# Connectors.net
KiCad netlist of a schematic drawn in Altium Designer
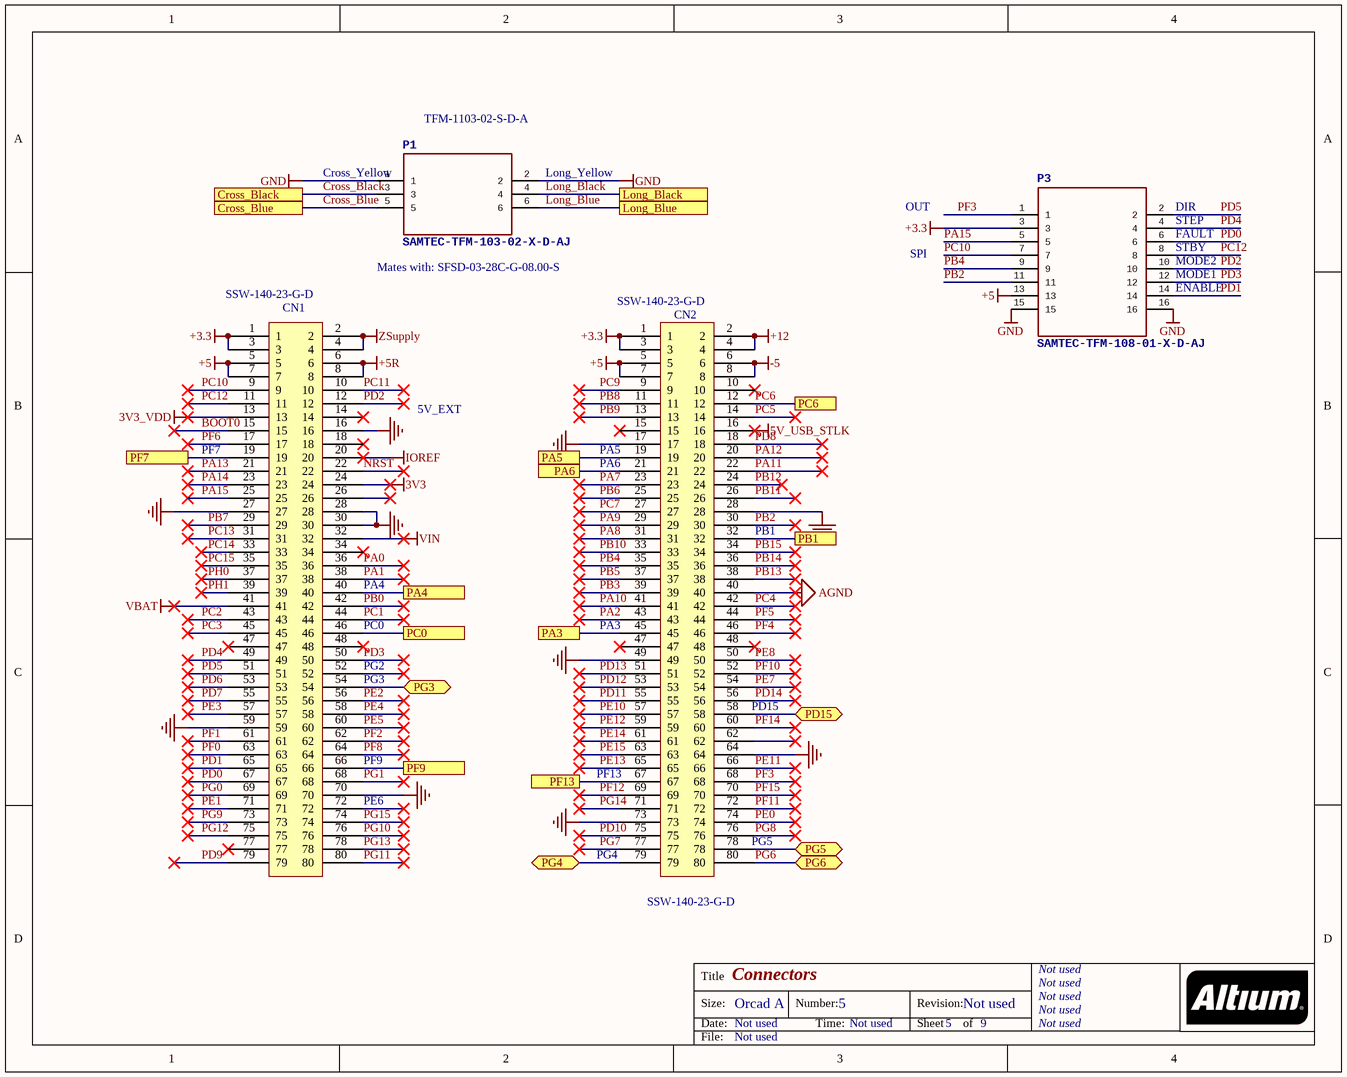
[diagram p0: Connectors.SchDoc]

(export (version "E")
  (design (tool "Eeschema 10.0.6"))
  (components
    (comp (ref "CN1")
      (value "SSW-140-23-G-D")
      (footprint "SSW-140-23-G-D")
      (description "80 Position Receptacle Connector Through Hole")
      (fields (field (name "SUPPLIER PART NUMBER 1") "SSW-140-23-G-D") (field (name "MANUFACTURER") "Samtec"))
      (libsource (lib "ZLS_Schematic_lib") (part "SSW-140-23-G-D"))
    )
    (comp (ref "CN2")
      (value "SSW-140-23-G-D")
      (footprint "SSW-140-23-G-D")
      (description "80 Position Receptacle Connector Through Hole")
      (fields (field (name "SUPPLIER PART NUMBER 1") "SSW-140-23-G-D") (field (name "MANUFACTURER") "Samtec"))
      (libsource (lib "ZLS_Schematic_lib") (part "SSW-140-23-G-D"))
    )
    (comp (ref "P1")
      (value "SAMTEC-TFM-103-02-X-D-AJ")
      (footprint "SAMTEC-TFM-103-02-X-D-A")
      (libsource (lib "SAMTEC-TFM-103-02-X-D-A") (part "SAMTEC-TFM-103-02-X-D-AJ"))
    )
    (comp (ref "P3")
      (value "SAMTEC-TFM-108-01-X-D-AJ")
      (footprint "SAMTEC-TFM-108-01-X-D-A")
      (libsource (lib "SAMTEC-TFM-108-01-X-D-A") (part "SAMTEC-TFM-108-01-X-D-AJ"))
    )
  )
  (nets
    (net (code "1") (name "+3.3") (class "Default")
      (node (ref "CN1") (pin "1") (pinfunction "1_1") (pintype "passive"))
      (node (ref "CN1") (pin "3") (pinfunction "3_3") (pintype "passive"))
      (node (ref "CN2") (pin "1") (pinfunction "1_1") (pintype "passive"))
      (node (ref "CN2") (pin "3") (pinfunction "3_3") (pintype "passive"))
      (node (ref "P3") (pin "3") (pinfunction "3_3") (pintype "passive"))
    )
    (net (code "2") (name "+5") (class "Default")
      (node (ref "CN1") (pin "5") (pinfunction "5_5") (pintype "passive"))
      (node (ref "CN1") (pin "7") (pinfunction "7_7") (pintype "passive"))
      (node (ref "CN2") (pin "5") (pinfunction "5_5") (pintype "passive"))
      (node (ref "CN2") (pin "7") (pinfunction "7_7") (pintype "passive"))
      (node (ref "P3") (pin "13") (pinfunction "13_13") (pintype "passive"))
    )
    (net (code "3") (name "+5R") (class "Default")
      (node (ref "CN1") (pin "6") (pinfunction "6_6") (pintype "passive"))
      (node (ref "CN1") (pin "8") (pinfunction "8_8") (pintype "passive"))
    )
    (net (code "4") (name "+12") (class "Default")
      (node (ref "CN2") (pin "2") (pinfunction "2_2") (pintype "passive"))
      (node (ref "CN2") (pin "4") (pinfunction "4_4") (pintype "passive"))
    )
    (net (code "5") (name "-5") (class "Default")
      (node (ref "CN2") (pin "6") (pinfunction "6_6") (pintype "passive"))
      (node (ref "CN2") (pin "8") (pinfunction "8_8") (pintype "passive"))
    )
    (net (code "6") (name "/BOOT0") (class "Default")
      (node (ref "CN1") (pin "15") (pinfunction "15_15") (pintype "passive+no_connect"))
    )
    (net (code "7") (name "/Cross_Black") (class "Default")
      (node (ref "P1") (pin "3") (pinfunction "3_3") (pintype "passive"))
    )
    (net (code "8") (name "/Cross_Blue") (class "Default")
      (node (ref "P1") (pin "5") (pinfunction "5_5") (pintype "passive"))
    )
    (net (code "9") (name "/Long_Black") (class "Default")
      (node (ref "P1") (pin "4") (pinfunction "4_4") (pintype "passive"))
    )
    (net (code "10") (name "/Long_Blue") (class "Default")
      (node (ref "P1") (pin "6") (pinfunction "6_6") (pintype "passive"))
    )
    (net (code "11") (name "/NRST") (class "Default")
      (node (ref "CN1") (pin "22") (pinfunction "22_22") (pintype "passive+no_connect"))
    )
    (net (code "12") (name "/PA0") (class "Default")
      (node (ref "CN1") (pin "36") (pinfunction "36_36") (pintype "passive+no_connect"))
    )
    (net (code "13") (name "/PA1") (class "Default")
      (node (ref "CN1") (pin "38") (pinfunction "38_38") (pintype "passive+no_connect"))
    )
    (net (code "14") (name "/PA2") (class "Default")
      (node (ref "CN2") (pin "43") (pinfunction "43_43") (pintype "passive+no_connect"))
    )
    (net (code "15") (name "/PA3") (class "Default")
      (node (ref "CN2") (pin "45") (pinfunction "45_45") (pintype "passive"))
    )
    (net (code "16") (name "/PA4") (class "Default")
      (node (ref "CN1") (pin "40") (pinfunction "40_40") (pintype "passive"))
    )
    (net (code "17") (name "/PA5") (class "Default")
      (node (ref "CN2") (pin "19") (pinfunction "19_19") (pintype "passive"))
    )
    (net (code "18") (name "/PA6") (class "Default")
      (node (ref "CN2") (pin "21") (pinfunction "21_21") (pintype "passive"))
    )
    (net (code "19") (name "/PA7") (class "Default")
      (node (ref "CN2") (pin "23") (pinfunction "23_23") (pintype "passive+no_connect"))
    )
    (net (code "20") (name "/PA8") (class "Default")
      (node (ref "CN2") (pin "31") (pinfunction "31_31") (pintype "passive+no_connect"))
    )
    (net (code "21") (name "/PA9") (class "Default")
      (node (ref "CN2") (pin "29") (pinfunction "29_29") (pintype "passive+no_connect"))
    )
    (net (code "22") (name "/PA10") (class "Default")
      (node (ref "CN2") (pin "41") (pinfunction "41_41") (pintype "passive+no_connect"))
    )
    (net (code "23") (name "/PA11") (class "Default")
      (node (ref "CN2") (pin "22") (pinfunction "22_22") (pintype "passive+no_connect"))
    )
    (net (code "24") (name "/PA12") (class "Default")
      (node (ref "CN2") (pin "20") (pinfunction "20_20") (pintype "passive+no_connect"))
    )
    (net (code "25") (name "/PA13") (class "Default")
      (node (ref "CN1") (pin "21") (pinfunction "21_21") (pintype "passive+no_connect"))
    )
    (net (code "26") (name "/PA14") (class "Default")
      (node (ref "CN1") (pin "23") (pinfunction "23_23") (pintype "passive+no_connect"))
    )
    (net (code "27") (name "/PA15") (class "Default")
      (node (ref "CN1") (pin "25") (pinfunction "25_25") (pintype "passive"))
      (node (ref "P3") (pin "5") (pinfunction "5_5") (pintype "passive"))
    )
    (net (code "28") (name "/PB0") (class "Default")
      (node (ref "CN1") (pin "42") (pinfunction "42_42") (pintype "passive+no_connect"))
    )
    (net (code "29") (name "/PB1") (class "Default")
      (node (ref "CN2") (pin "32") (pinfunction "32_32") (pintype "passive"))
    )
    (net (code "30") (name "/PB2") (class "Default")
      (node (ref "CN2") (pin "30") (pinfunction "30_30") (pintype "passive"))
      (node (ref "P3") (pin "11") (pinfunction "11_11") (pintype "passive"))
    )
    (net (code "31") (name "/PB3") (class "Default")
      (node (ref "CN2") (pin "39") (pinfunction "39_39") (pintype "passive+no_connect"))
    )
    (net (code "32") (name "/PB4") (class "Default")
      (node (ref "CN2") (pin "35") (pinfunction "35_35") (pintype "passive"))
      (node (ref "P3") (pin "9") (pinfunction "9_9") (pintype "passive"))
    )
    (net (code "33") (name "/PB5") (class "Default")
      (node (ref "CN2") (pin "37") (pinfunction "37_37") (pintype "passive+no_connect"))
    )
    (net (code "34") (name "/PB6") (class "Default")
      (node (ref "CN2") (pin "25") (pinfunction "25_25") (pintype "passive+no_connect"))
    )
    (net (code "35") (name "/PB7") (class "Default")
      (node (ref "CN1") (pin "29") (pinfunction "29_29") (pintype "passive+no_connect"))
    )
    (net (code "36") (name "/PB8") (class "Default")
      (node (ref "CN2") (pin "11") (pinfunction "11_11") (pintype "passive+no_connect"))
    )
    (net (code "37") (name "/PB9") (class "Default")
      (node (ref "CN2") (pin "13") (pinfunction "13_13") (pintype "passive+no_connect"))
    )
    (net (code "38") (name "/PB10") (class "Default")
      (node (ref "CN2") (pin "33") (pinfunction "33_33") (pintype "passive+no_connect"))
    )
    (net (code "39") (name "/PB11") (class "Default")
      (node (ref "CN2") (pin "26") (pinfunction "26_26") (pintype "passive+no_connect"))
    )
    (net (code "40") (name "/PB12") (class "Default")
      (node (ref "CN2") (pin "24") (pinfunction "24_24") (pintype "passive+no_connect"))
    )
    (net (code "41") (name "/PB13") (class "Default")
      (node (ref "CN2") (pin "38") (pinfunction "38_38") (pintype "passive+no_connect"))
    )
    (net (code "42") (name "/PB14") (class "Default")
      (node (ref "CN2") (pin "36") (pinfunction "36_36") (pintype "passive+no_connect"))
    )
    (net (code "43") (name "/PB15") (class "Default")
      (node (ref "CN2") (pin "34") (pinfunction "34_34") (pintype "passive+no_connect"))
    )
    (net (code "44") (name "/PC0") (class "Default")
      (node (ref "CN1") (pin "46") (pinfunction "46_46") (pintype "passive"))
    )
    (net (code "45") (name "/PC1") (class "Default")
      (node (ref "CN1") (pin "44") (pinfunction "44_44") (pintype "passive+no_connect"))
    )
    (net (code "46") (name "/PC2") (class "Default")
      (node (ref "CN1") (pin "43") (pinfunction "43_43") (pintype "passive+no_connect"))
    )
    (net (code "47") (name "/PC3") (class "Default")
      (node (ref "CN1") (pin "45") (pinfunction "45_45") (pintype "passive+no_connect"))
    )
    (net (code "48") (name "/PC4") (class "Default")
      (node (ref "CN2") (pin "42") (pinfunction "42_42") (pintype "passive+no_connect"))
    )
    (net (code "49") (name "/PC5") (class "Default")
      (node (ref "CN2") (pin "14") (pinfunction "14_14") (pintype "passive+no_connect"))
    )
    (net (code "50") (name "/PC6") (class "Default")
      (node (ref "CN2") (pin "12") (pinfunction "12_12") (pintype "passive"))
    )
    (net (code "51") (name "/PC7") (class "Default")
      (node (ref "CN2") (pin "27") (pinfunction "27_27") (pintype "passive+no_connect"))
    )
    (net (code "52") (name "/PC9") (class "Default")
      (node (ref "CN2") (pin "9") (pinfunction "9_9") (pintype "passive+no_connect"))
    )
    (net (code "53") (name "/PC10") (class "Default")
      (node (ref "CN1") (pin "9") (pinfunction "9_9") (pintype "passive"))
      (node (ref "P3") (pin "7") (pinfunction "7_7") (pintype "passive"))
    )
    (net (code "54") (name "/PC11") (class "Default")
      (node (ref "CN1") (pin "10") (pinfunction "10_10") (pintype "passive+no_connect"))
    )
    (net (code "55") (name "/PC12") (class "Default")
      (node (ref "CN1") (pin "11") (pinfunction "11_11") (pintype "passive"))
      (node (ref "P3") (pin "8") (pinfunction "8_8") (pintype "passive"))
    )
    (net (code "56") (name "/PC13") (class "Default")
      (node (ref "CN1") (pin "31") (pinfunction "31_31") (pintype "passive+no_connect"))
    )
    (net (code "57") (name "/PC14") (class "Default")
      (node (ref "CN1") (pin "33") (pinfunction "33_33") (pintype "passive+no_connect"))
    )
    (net (code "58") (name "/PC15") (class "Default")
      (node (ref "CN1") (pin "35") (pinfunction "35_35") (pintype "passive+no_connect"))
    )
    (net (code "59") (name "/PD0") (class "Default")
      (node (ref "CN1") (pin "67") (pinfunction "67_67") (pintype "passive"))
      (node (ref "P3") (pin "6") (pinfunction "6_6") (pintype "passive"))
    )
    (net (code "60") (name "/PD1") (class "Default")
      (node (ref "CN1") (pin "65") (pinfunction "65_65") (pintype "passive"))
      (node (ref "P3") (pin "14") (pinfunction "14_14") (pintype "passive"))
    )
    (net (code "61") (name "/PD2") (class "Default")
      (node (ref "CN1") (pin "12") (pinfunction "12_12") (pintype "passive"))
      (node (ref "P3") (pin "10") (pinfunction "10_10") (pintype "passive"))
    )
    (net (code "62") (name "/PD3") (class "Default")
      (node (ref "CN1") (pin "50") (pinfunction "50_50") (pintype "passive"))
      (node (ref "P3") (pin "12") (pinfunction "12_12") (pintype "passive"))
    )
    (net (code "63") (name "/PD4") (class "Default")
      (node (ref "CN1") (pin "49") (pinfunction "49_49") (pintype "passive"))
      (node (ref "P3") (pin "4") (pinfunction "4_4") (pintype "passive"))
    )
    (net (code "64") (name "/PD5") (class "Default")
      (node (ref "CN1") (pin "51") (pinfunction "51_51") (pintype "passive"))
      (node (ref "P3") (pin "2") (pinfunction "2_2") (pintype "passive"))
    )
    (net (code "65") (name "/PD6") (class "Default")
      (node (ref "CN1") (pin "53") (pinfunction "53_53") (pintype "passive+no_connect"))
    )
    (net (code "66") (name "/PD7") (class "Default")
      (node (ref "CN1") (pin "55") (pinfunction "55_55") (pintype "passive+no_connect"))
    )
    (net (code "67") (name "/PD8") (class "Default")
      (node (ref "CN2") (pin "18") (pinfunction "18_18") (pintype "passive+no_connect"))
    )
    (net (code "68") (name "/PD9") (class "Default")
      (node (ref "CN1") (pin "79") (pinfunction "79_79") (pintype "passive+no_connect"))
    )
    (net (code "69") (name "/PD10") (class "Default")
      (node (ref "CN2") (pin "75") (pinfunction "75_75") (pintype "passive+no_connect"))
    )
    (net (code "70") (name "/PD11") (class "Default")
      (node (ref "CN2") (pin "55") (pinfunction "55_55") (pintype "passive+no_connect"))
    )
    (net (code "71") (name "/PD12") (class "Default")
      (node (ref "CN2") (pin "53") (pinfunction "53_53") (pintype "passive+no_connect"))
    )
    (net (code "72") (name "/PD13") (class "Default")
      (node (ref "CN2") (pin "51") (pinfunction "51_51") (pintype "passive+no_connect"))
    )
    (net (code "73") (name "/PD14") (class "Default")
      (node (ref "CN2") (pin "56") (pinfunction "56_56") (pintype "passive+no_connect"))
    )
    (net (code "74") (name "/PD15") (class "Default")
      (node (ref "CN2") (pin "58") (pinfunction "58_58") (pintype "passive"))
    )
    (net (code "75") (name "/PE0") (class "Default")
      (node (ref "CN2") (pin "74") (pinfunction "74_74") (pintype "passive+no_connect"))
    )
    (net (code "76") (name "/PE1") (class "Default")
      (node (ref "CN1") (pin "71") (pinfunction "71_71") (pintype "passive+no_connect"))
    )
    (net (code "77") (name "/PE2") (class "Default")
      (node (ref "CN1") (pin "56") (pinfunction "56_56") (pintype "passive+no_connect"))
    )
    (net (code "78") (name "/PE3") (class "Default")
      (node (ref "CN1") (pin "57") (pinfunction "57_57") (pintype "passive+no_connect"))
    )
    (net (code "79") (name "/PE4") (class "Default")
      (node (ref "CN1") (pin "58") (pinfunction "58_58") (pintype "passive+no_connect"))
    )
    (net (code "80") (name "/PE5") (class "Default")
      (node (ref "CN1") (pin "60") (pinfunction "60_60") (pintype "passive+no_connect"))
    )
    (net (code "81") (name "/PE7") (class "Default")
      (node (ref "CN2") (pin "54") (pinfunction "54_54") (pintype "passive+no_connect"))
    )
    (net (code "82") (name "/PE8") (class "Default")
      (node (ref "CN2") (pin "50") (pinfunction "50_50") (pintype "passive+no_connect"))
    )
    (net (code "83") (name "/PE10") (class "Default")
      (node (ref "CN2") (pin "57") (pinfunction "57_57") (pintype "passive+no_connect"))
    )
    (net (code "84") (name "/PE11") (class "Default")
      (node (ref "CN2") (pin "66") (pinfunction "66_66") (pintype "passive+no_connect"))
    )
    (net (code "85") (name "/PE12") (class "Default")
      (node (ref "CN2") (pin "59") (pinfunction "59_59") (pintype "passive+no_connect"))
    )
    (net (code "86") (name "/PE13") (class "Default")
      (node (ref "CN2") (pin "65") (pinfunction "65_65") (pintype "passive+no_connect"))
    )
    (net (code "87") (name "/PE14") (class "Default")
      (node (ref "CN2") (pin "61") (pinfunction "61_61") (pintype "passive+no_connect"))
    )
    (net (code "88") (name "/PE15") (class "Default")
      (node (ref "CN2") (pin "63") (pinfunction "63_63") (pintype "passive+no_connect"))
    )
    (net (code "89") (name "/PF0") (class "Default")
      (node (ref "CN1") (pin "63") (pinfunction "63_63") (pintype "passive+no_connect"))
    )
    (net (code "90") (name "/PF1") (class "Default")
      (node (ref "CN1") (pin "61") (pinfunction "61_61") (pintype "passive+no_connect"))
    )
    (net (code "91") (name "/PF2") (class "Default")
      (node (ref "CN1") (pin "62") (pinfunction "62_62") (pintype "passive+no_connect"))
    )
    (net (code "92") (name "/PF3") (class "Default")
      (node (ref "CN2") (pin "68") (pinfunction "68_68") (pintype "passive"))
      (node (ref "P3") (pin "1") (pinfunction "1_1") (pintype "passive"))
    )
    (net (code "93") (name "/PF4") (class "Default")
      (node (ref "CN2") (pin "46") (pinfunction "46_46") (pintype "passive+no_connect"))
    )
    (net (code "94") (name "/PF5") (class "Default")
      (node (ref "CN2") (pin "44") (pinfunction "44_44") (pintype "passive+no_connect"))
    )
    (net (code "95") (name "/PF6") (class "Default")
      (node (ref "CN1") (pin "17") (pinfunction "17_17") (pintype "passive+no_connect"))
    )
    (net (code "96") (name "/PF7") (class "Default")
      (node (ref "CN1") (pin "19") (pinfunction "19_19") (pintype "passive"))
    )
    (net (code "97") (name "/PF8") (class "Default")
      (node (ref "CN1") (pin "64") (pinfunction "64_64") (pintype "passive+no_connect"))
    )
    (net (code "98") (name "/PF9") (class "Default")
      (node (ref "CN1") (pin "66") (pinfunction "66_66") (pintype "passive"))
    )
    (net (code "99") (name "/PF10") (class "Default")
      (node (ref "CN2") (pin "52") (pinfunction "52_52") (pintype "passive+no_connect"))
    )
    (net (code "100") (name "/PF11") (class "Default")
      (node (ref "CN2") (pin "72") (pinfunction "72_72") (pintype "passive+no_connect"))
    )
    (net (code "101") (name "/PF12") (class "Default")
      (node (ref "CN2") (pin "69") (pinfunction "69_69") (pintype "passive+no_connect"))
    )
    (net (code "102") (name "/PF13") (class "Default")
      (node (ref "CN2") (pin "67") (pinfunction "67_67") (pintype "passive"))
    )
    (net (code "103") (name "/PF14") (class "Default")
      (node (ref "CN2") (pin "60") (pinfunction "60_60") (pintype "passive+no_connect"))
    )
    (net (code "104") (name "/PF15") (class "Default")
      (node (ref "CN2") (pin "70") (pinfunction "70_70") (pintype "passive+no_connect"))
    )
    (net (code "105") (name "/PG0") (class "Default")
      (node (ref "CN1") (pin "69") (pinfunction "69_69") (pintype "passive+no_connect"))
    )
    (net (code "106") (name "/PG1") (class "Default")
      (node (ref "CN1") (pin "68") (pinfunction "68_68") (pintype "passive+no_connect"))
    )
    (net (code "107") (name "/PG3") (class "Default")
      (node (ref "CN1") (pin "54") (pinfunction "54_54") (pintype "passive"))
    )
    (net (code "108") (name "/PG4") (class "Default")
      (node (ref "CN2") (pin "79") (pinfunction "79_79") (pintype "passive"))
    )
    (net (code "109") (name "/PG5") (class "Default")
      (node (ref "CN2") (pin "78") (pinfunction "78_78") (pintype "passive"))
    )
    (net (code "110") (name "/PG6") (class "Default")
      (node (ref "CN2") (pin "80") (pinfunction "80_80") (pintype "passive"))
    )
    (net (code "111") (name "/PG7") (class "Default")
      (node (ref "CN2") (pin "77") (pinfunction "77_77") (pintype "passive+no_connect"))
    )
    (net (code "112") (name "/PG8") (class "Default")
      (node (ref "CN2") (pin "76") (pinfunction "76_76") (pintype "passive+no_connect"))
    )
    (net (code "113") (name "/PG9") (class "Default")
      (node (ref "CN1") (pin "73") (pinfunction "73_73") (pintype "passive+no_connect"))
    )
    (net (code "114") (name "/PG10") (class "Default")
      (node (ref "CN1") (pin "76") (pinfunction "76_76") (pintype "passive+no_connect"))
    )
    (net (code "115") (name "/PG11") (class "Default")
      (node (ref "CN1") (pin "80") (pinfunction "80_80") (pintype "passive+no_connect"))
    )
    (net (code "116") (name "/PG12") (class "Default")
      (node (ref "CN1") (pin "75") (pinfunction "75_75") (pintype "passive+no_connect"))
    )
    (net (code "117") (name "/PG13") (class "Default")
      (node (ref "CN1") (pin "78") (pinfunction "78_78") (pintype "passive+no_connect"))
    )
    (net (code "118") (name "/PG14") (class "Default")
      (node (ref "CN2") (pin "71") (pinfunction "71_71") (pintype "passive+no_connect"))
    )
    (net (code "119") (name "/PG15") (class "Default")
      (node (ref "CN1") (pin "74") (pinfunction "74_74") (pintype "passive+no_connect"))
    )
    (net (code "120") (name "/PH0") (class "Default")
      (node (ref "CN1") (pin "37") (pinfunction "37_37") (pintype "passive+no_connect"))
    )
    (net (code "121") (name "/PH1") (class "Default")
      (node (ref "CN1") (pin "39") (pinfunction "39_39") (pintype "passive+no_connect"))
    )
    (net (code "122") (name "3V3") (class "Default")
      (node (ref "CN1") (pin "24") (pinfunction "24_24") (pintype "passive"))
    )
    (net (code "123") (name "3V3_VDD") (class "Default")
      (node (ref "CN1") (pin "13") (pinfunction "13_13") (pintype "passive"))
    )
    (net (code "124") (name "5V_USB_STLK") (class "Default")
      (node (ref "CN2") (pin "16") (pinfunction "16_16") (pintype "passive"))
    )
    (net (code "125") (name "AGND") (class "Default")
      (node (ref "CN2") (pin "40") (pinfunction "40_40") (pintype "passive"))
    )
    (net (code "126") (name "GND") (class "Default")
      (node (ref "CN1") (pin "16") (pinfunction "16_16") (pintype "passive"))
      (node (ref "CN1") (pin "27") (pinfunction "27_27") (pintype "passive"))
      (node (ref "CN1") (pin "28") (pinfunction "28_28") (pintype "passive"))
      (node (ref "CN1") (pin "30") (pinfunction "30_30") (pintype "passive"))
      (node (ref "CN1") (pin "59") (pinfunction "59_59") (pintype "passive"))
      (node (ref "CN1") (pin "70") (pinfunction "70_70") (pintype "passive"))
      (node (ref "CN2") (pin "17") (pinfunction "17_17") (pintype "passive"))
      (node (ref "CN2") (pin "28") (pinfunction "28_28") (pintype "passive"))
      (node (ref "CN2") (pin "49") (pinfunction "49_49") (pintype "passive"))
      (node (ref "CN2") (pin "64") (pinfunction "64_64") (pintype "passive"))
      (node (ref "CN2") (pin "73") (pinfunction "73_73") (pintype "passive"))
      (node (ref "P1") (pin "1") (pinfunction "1_1") (pintype "passive"))
      (node (ref "P1") (pin "2") (pinfunction "2_2") (pintype "passive"))
      (node (ref "P3") (pin "15") (pinfunction "15_15") (pintype "passive"))
      (node (ref "P3") (pin "16") (pinfunction "16_16") (pintype "passive"))
    )
    (net (code "127") (name "IOREF") (class "Default")
      (node (ref "CN1") (pin "20") (pinfunction "20_20") (pintype "passive"))
    )
    (net (code "128") (name "VBAT") (class "Default")
      (node (ref "CN1") (pin "41") (pinfunction "41_41") (pintype "passive"))
    )
    (net (code "129") (name "VIN") (class "Default")
      (node (ref "CN1") (pin "32") (pinfunction "32_32") (pintype "passive"))
    )
    (net (code "130") (name "ZSupply") (class "Default")
      (node (ref "CN1") (pin "2") (pinfunction "2_2") (pintype "passive"))
      (node (ref "CN1") (pin "4") (pinfunction "4_4") (pintype "passive"))
    )
    (net (code "131") (name "unconnected-(CN1-Pad14)") (class "Default")
      (node (ref "CN1") (pin "14") (pinfunction "14_14") (pintype "passive+no_connect"))
    )
    (net (code "132") (name "unconnected-(CN1-Pad18)") (class "Default")
      (node (ref "CN1") (pin "18") (pinfunction "18_18") (pintype "passive+no_connect"))
    )
    (net (code "133") (name "unconnected-(CN1-Pad26)") (class "Default")
      (node (ref "CN1") (pin "26") (pinfunction "26_26") (pintype "passive+no_connect"))
    )
    (net (code "134") (name "unconnected-(CN1-Pad34)") (class "Default")
      (node (ref "CN1") (pin "34") (pinfunction "34_34") (pintype "passive+no_connect"))
    )
    (net (code "135") (name "unconnected-(CN1-Pad47)") (class "Default")
      (node (ref "CN1") (pin "47") (pinfunction "47_47") (pintype "passive+no_connect"))
    )
    (net (code "136") (name "unconnected-(CN1-Pad48)") (class "Default")
      (node (ref "CN1") (pin "48") (pinfunction "48_48") (pintype "passive+no_connect"))
    )
    (net (code "137") (name "unconnected-(CN1-Pad52)") (class "Default")
      (node (ref "CN1") (pin "52") (pinfunction "52_52") (pintype "passive+no_connect"))
    )
    (net (code "138") (name "unconnected-(CN1-Pad72)") (class "Default")
      (node (ref "CN1") (pin "72") (pinfunction "72_72") (pintype "passive+no_connect"))
    )
    (net (code "139") (name "unconnected-(CN1-Pad77)") (class "Default")
      (node (ref "CN1") (pin "77") (pinfunction "77_77") (pintype "passive+no_connect"))
    )
    (net (code "140") (name "unconnected-(CN2-Pad10)") (class "Default")
      (node (ref "CN2") (pin "10") (pinfunction "10_10") (pintype "passive+no_connect"))
    )
    (net (code "141") (name "unconnected-(CN2-Pad15)") (class "Default")
      (node (ref "CN2") (pin "15") (pinfunction "15_15") (pintype "passive+no_connect"))
    )
    (net (code "142") (name "unconnected-(CN2-Pad47)") (class "Default")
      (node (ref "CN2") (pin "47") (pinfunction "47_47") (pintype "passive+no_connect"))
    )
    (net (code "143") (name "unconnected-(CN2-Pad48)") (class "Default")
      (node (ref "CN2") (pin "48") (pinfunction "48_48") (pintype "passive+no_connect"))
    )
    (net (code "144") (name "unconnected-(CN2-Pad62)") (class "Default")
      (node (ref "CN2") (pin "62") (pinfunction "62_62") (pintype "passive+no_connect"))
    )
  )
)
